# Z_Probing_Add_on_Board.net
KiCad netlist of a schematic drawn in EAGLE
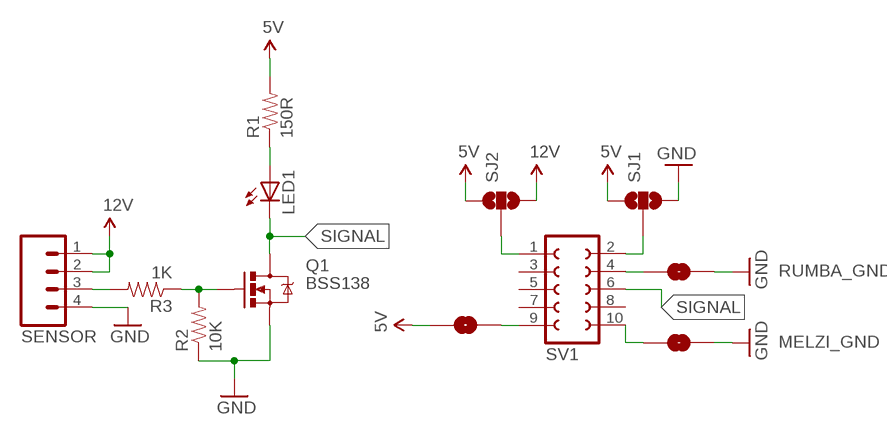
[diagram p0: schematic, sheet 1]

(export (version "E")
  (design (tool "Eeschema 10.0.6"))
  (components
    (comp (ref "LED1")
      (value "LEDCHIPLED_0805")
      (footprint "eagle-import:CHIPLED_0805")
      (libsource (lib "eagle-import") (part "LEDCHIPLED_0805"))
    )
    (comp (ref "MELZI_GND")
      (value "SOLDERJUMPERNO")
      (footprint "eagle-import:SJ_2S-NO")
      (libsource (lib "eagle-import") (part "SOLDERJUMPERNO"))
    )
    (comp (ref "MELZI_GND1")
      (value "SOLDERJUMPERNO")
      (footprint "eagle-import:SJ_2S-NO")
      (libsource (lib "eagle-import") (part "SOLDERJUMPERNO"))
    )
    (comp (ref "Q1")
      (value "BSS138")
      (footprint "eagle-import:SOT23")
      (libsource (lib "eagle-import") (part "MOSFET-NCHANNELBSS123LT1G"))
    )
    (comp (ref "R1")
      (value "150R")
      (footprint "eagle-import:0805")
      (libsource (lib "eagle-import") (part "0.3OHM-1/8W-1%(0805)"))
    )
    (comp (ref "R2")
      (value "10K")
      (footprint "eagle-import:0805")
      (libsource (lib "eagle-import") (part "0.3OHM-1/8W-1%(0805)"))
    )
    (comp (ref "R3")
      (value "1K")
      (footprint "eagle-import:0805")
      (libsource (lib "eagle-import") (part "0.3OHM-1/8W-1%(0805)"))
    )
    (comp (ref "RUMBA_GND")
      (value "SOLDERJUMPERNO")
      (footprint "eagle-import:SJ_2S-NO")
      (libsource (lib "eagle-import") (part "SOLDERJUMPERNO"))
    )
    (comp (ref "SENSOR")
      (value "M04PTH")
      (footprint "eagle-import:1X04")
      (libsource (lib "eagle-import") (part "M04PTH"))
    )
    (comp (ref "SJ1")
      (value "SOLDERJUMPER_2WAYS")
      (footprint "eagle-import:SJ_3")
      (libsource (lib "eagle-import") (part "SOLDERJUMPER_2WAYS"))
    )
    (comp (ref "SJ2")
      (value "SOLDERJUMPER_2WAYS")
      (footprint "eagle-import:SJ_3")
      (libsource (lib "eagle-import") (part "SOLDERJUMPER_2WAYS"))
    )
    (comp (ref "SV1")
      (value "FE05-2")
      (footprint "eagle-import:FE05-2")
      (libsource (lib "eagle-import") (part "FE05-2"))
    )
  )
  (nets
    (net (code "1") (name "5V") (class "Default")
      (node (ref "MELZI_GND1") (pin "1") (pinfunction "1_1") (pintype "passive"))
      (node (ref "R1") (pin "2") (pinfunction "2_2") (pintype "passive"))
      (node (ref "SJ1") (pin "1") (pinfunction "1_1") (pintype "passive"))
      (node (ref "SJ2") (pin "1") (pinfunction "1_1") (pintype "passive"))
    )
    (net (code "2") (name "12V") (class "Default")
      (node (ref "SENSOR") (pin "1") (pinfunction "1_1") (pintype "passive"))
      (node (ref "SENSOR") (pin "2") (pinfunction "2_2") (pintype "passive"))
      (node (ref "SJ2") (pin "3") (pinfunction "3_3") (pintype "passive"))
    )
    (net (code "3") (name "GND") (class "Default")
      (node (ref "MELZI_GND") (pin "2") (pinfunction "2_2") (pintype "passive"))
      (node (ref "Q1") (pin "2") (pinfunction "S_2") (pintype "passive"))
      (node (ref "R2") (pin "1") (pinfunction "1_1") (pintype "passive"))
      (node (ref "RUMBA_GND") (pin "2") (pinfunction "2_2") (pintype "passive"))
      (node (ref "SENSOR") (pin "4") (pinfunction "4_4") (pintype "passive"))
      (node (ref "SJ1") (pin "3") (pinfunction "3_3") (pintype "passive"))
    )
    (net (code "4") (name "Net-(LED1-PadA)") (class "Default")
      (node (ref "LED1") (pin "A") (pinfunction "A_A") (pintype "passive"))
      (node (ref "R1") (pin "1") (pinfunction "1_1") (pintype "passive"))
    )
    (net (code "5") (name "Net-(MELZI_GND-Pad1)") (class "Default")
      (node (ref "MELZI_GND") (pin "1") (pinfunction "1_1") (pintype "passive"))
      (node (ref "SV1") (pin "10") (pinfunction "10_10") (pintype "passive"))
    )
    (net (code "6") (name "Net-(MELZI_GND1-Pad2)") (class "Default")
      (node (ref "MELZI_GND1") (pin "2") (pinfunction "2_2") (pintype "passive"))
      (node (ref "SV1") (pin "9") (pinfunction "9_9") (pintype "passive"))
    )
    (net (code "7") (name "Net-(Q1-G)") (class "Default")
      (node (ref "Q1") (pin "1") (pinfunction "G_1") (pintype "passive"))
      (node (ref "R2") (pin "2") (pinfunction "2_2") (pintype "passive"))
      (node (ref "R3") (pin "1") (pinfunction "1_1") (pintype "passive"))
    )
    (net (code "8") (name "Net-(R3-Pad2)") (class "Default")
      (node (ref "R3") (pin "2") (pinfunction "2_2") (pintype "passive"))
      (node (ref "SENSOR") (pin "3") (pinfunction "3_3") (pintype "passive"))
    )
    (net (code "9") (name "Net-(RUMBA_GND-Pad1)") (class "Default")
      (node (ref "RUMBA_GND") (pin "1") (pinfunction "1_1") (pintype "passive"))
      (node (ref "SV1") (pin "4") (pinfunction "4_4") (pintype "passive"))
    )
    (net (code "10") (name "Net-(SJ1-Pad2)") (class "Default")
      (node (ref "SJ1") (pin "2") (pinfunction "2_2") (pintype "passive"))
      (node (ref "SV1") (pin "2") (pinfunction "2_2") (pintype "passive"))
    )
    (net (code "11") (name "Net-(SJ2-Pad2)") (class "Default")
      (node (ref "SJ2") (pin "2") (pinfunction "2_2") (pintype "passive"))
      (node (ref "SV1") (pin "1") (pinfunction "1_1") (pintype "passive"))
    )
    (net (code "12") (name "SIGNAL") (class "Default")
      (node (ref "LED1") (pin "C") (pinfunction "C_C") (pintype "passive"))
      (node (ref "Q1") (pin "3") (pinfunction "D_3") (pintype "passive"))
    )
    (net (code "13") (name "unconnected-(SV1-Pad3)") (class "Default")
      (node (ref "SV1") (pin "3") (pinfunction "3_3") (pintype "passive"))
    )
    (net (code "14") (name "unconnected-(SV1-Pad5)") (class "Default")
      (node (ref "SV1") (pin "5") (pinfunction "5_5") (pintype "passive"))
    )
    (net (code "15") (name "unconnected-(SV1-Pad6)") (class "Default")
      (node (ref "SV1") (pin "6") (pinfunction "6_6") (pintype "passive"))
    )
    (net (code "16") (name "unconnected-(SV1-Pad7)") (class "Default")
      (node (ref "SV1") (pin "7") (pinfunction "7_7") (pintype "passive"))
    )
    (net (code "17") (name "unconnected-(SV1-Pad8)") (class "Default")
      (node (ref "SV1") (pin "8") (pinfunction "8_8") (pintype "passive"))
    )
  )
)
